# Keyboard_Controller.net
KiCad netlist of a schematic drawn in EAGLE
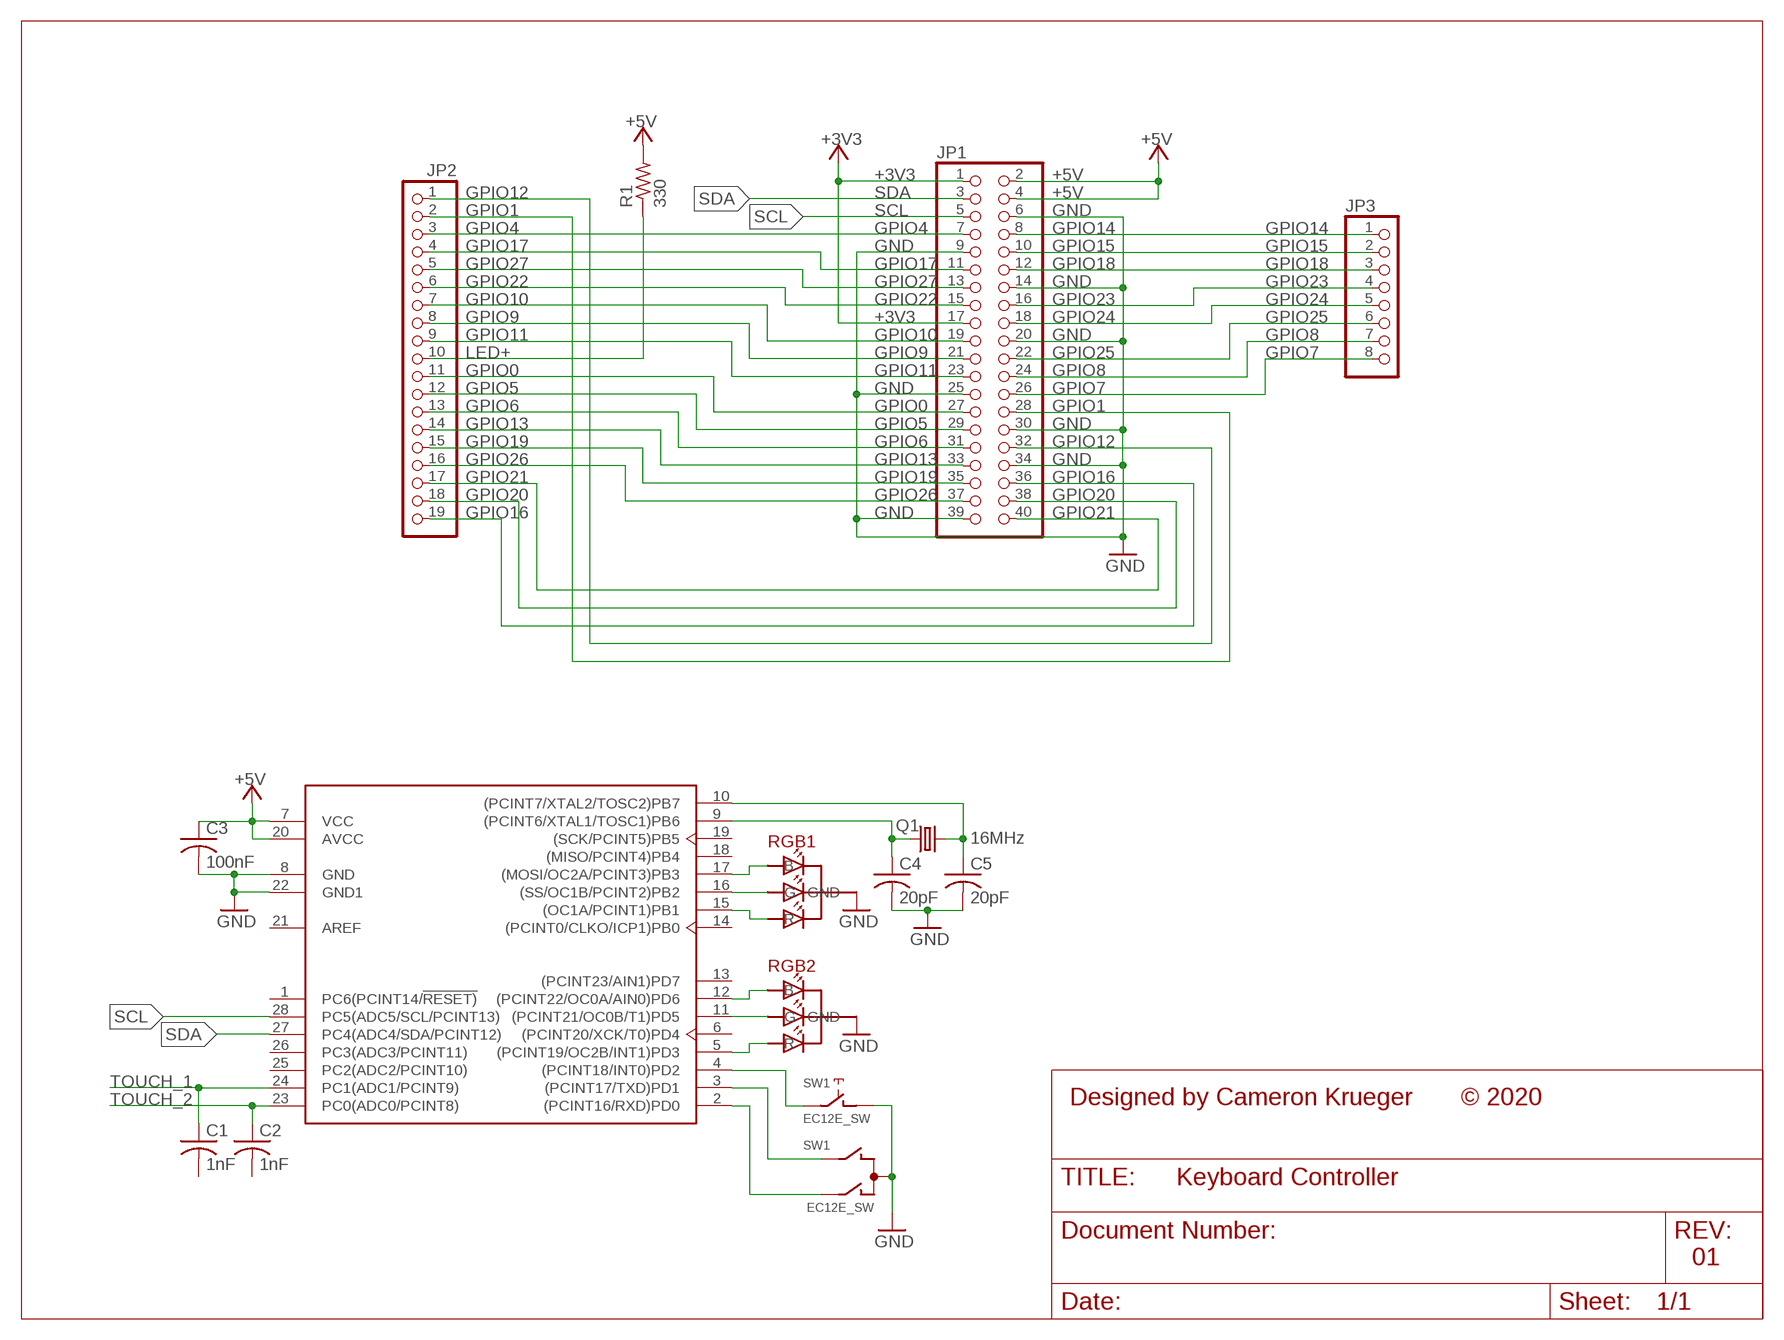
[diagram p0: schematic, sheet 1]

(export (version "E")
  (design (tool "Eeschema 10.0.6"))
  (components
    (comp (ref "C1")
      (value "1nF")
      (footprint "eagle-import:C025-030X050")
      (libsource (lib "eagle-import") (part "C-US025-030X050"))
    )
    (comp (ref "C2")
      (value "1nF")
      (footprint "eagle-import:C025-030X050")
      (libsource (lib "eagle-import") (part "C-US025-030X050"))
    )
    (comp (ref "C3")
      (value "100nF")
      (footprint "eagle-import:C050-024X044")
      (libsource (lib "eagle-import") (part "C-US050-024X044"))
    )
    (comp (ref "C4")
      (value "20pF")
      (footprint "eagle-import:C025-030X050")
      (libsource (lib "eagle-import") (part "C-US025-030X050"))
    )
    (comp (ref "C5")
      (value "20pF")
      (footprint "eagle-import:C025-030X050")
      (libsource (lib "eagle-import") (part "C-US025-030X050"))
    )
    (comp (ref "JP1")
      (value "PINHD-2X20")
      (footprint "eagle-import:2X20")
      (libsource (lib "eagle-import") (part "PINHD-2X20"))
    )
    (comp (ref "JP2")
      (value "PINHD-1X19")
      (footprint "eagle-import:1X19")
      (libsource (lib "eagle-import") (part "PINHD-1X19"))
    )
    (comp (ref "JP3")
      (value "PINHD-1X8")
      (footprint "eagle-import:1X08")
      (libsource (lib "eagle-import") (part "PINHD-1X8"))
    )
    (comp (ref "Q1")
      (value "16MHz")
      (footprint "eagle-import:HC49U-V")
      (libsource (lib "eagle-import") (part "CRYSTALHC49U-V"))
    )
    (comp (ref "R1")
      (value "330")
      (footprint "eagle-import:0207_10")
      (libsource (lib "eagle-import") (part "R-US_0207/10"))
    )
    (comp (ref "RGB1")
      (value "5MMRGBLED")
      (footprint "eagle-import:LED5MMRGB")
      (libsource (lib "eagle-import") (part "5MMRGBLED"))
    )
    (comp (ref "RGB2")
      (value "5MMRGBLED")
      (footprint "eagle-import:LED5MMRGB")
      (libsource (lib "eagle-import") (part "5MMRGBLED"))
    )
    (comp (ref "SW1")
      (value "EC12E_SW")
      (footprint "eagle-import:ALPS_EC12E_SW")
      (fields (field (name "MPN") "EC12E2424407"))
      (libsource (lib "eagle-import") (part "EC12E_SW"))
    )
    (comp (ref "U2")
      (value "ATMEGA328P-PU")
      (footprint "eagle-import:DIP-28")
      (fields
        (field (name "DIGIKEY_PART_NUMBER") "ATMEGA328P-PU-ND")
        (field (name "MANUFACTURER") "Microchip Technology")
        (field (name "CREATED_BY") "PCBLayout.com")
      )
      (libsource (lib "eagle-import") (part "ATMEGA328P-PU"))
    )
  )
  (nets
    (net (code "1") (name "+3V3") (class "Default")
      (node (ref "JP1") (pin "1") (pinfunction "1_1") (pintype "passive"))
      (node (ref "JP1") (pin "17") (pinfunction "17_17") (pintype "passive"))
    )
    (net (code "2") (name "+5V") (class "Default")
      (node (ref "C3") (pin "1") (pinfunction "1_1") (pintype "passive"))
      (node (ref "JP1") (pin "2") (pinfunction "2_2") (pintype "passive"))
      (node (ref "JP1") (pin "4") (pinfunction "4_4") (pintype "passive"))
      (node (ref "R1") (pin "2") (pinfunction "2_2") (pintype "passive"))
      (node (ref "U2") (pin "20") (pinfunction "AVCC_20") (pintype "power_in"))
      (node (ref "U2") (pin "7") (pinfunction "VCC_7") (pintype "power_in"))
    )
    (net (code "3") (name "/GPIO0") (class "Default")
      (node (ref "JP1") (pin "27") (pinfunction "27_27") (pintype "passive"))
      (node (ref "JP2") (pin "11") (pinfunction "11_11") (pintype "passive"))
    )
    (net (code "4") (name "/GPIO1") (class "Default")
      (node (ref "JP1") (pin "28") (pinfunction "28_28") (pintype "passive"))
      (node (ref "JP2") (pin "2") (pinfunction "2_2") (pintype "passive"))
    )
    (net (code "5") (name "/GPIO4") (class "Default")
      (node (ref "JP1") (pin "7") (pinfunction "7_7") (pintype "passive"))
      (node (ref "JP2") (pin "3") (pinfunction "3_3") (pintype "passive"))
    )
    (net (code "6") (name "/GPIO5") (class "Default")
      (node (ref "JP1") (pin "29") (pinfunction "29_29") (pintype "passive"))
      (node (ref "JP2") (pin "12") (pinfunction "12_12") (pintype "passive"))
    )
    (net (code "7") (name "/GPIO6") (class "Default")
      (node (ref "JP1") (pin "31") (pinfunction "31_31") (pintype "passive"))
      (node (ref "JP2") (pin "13") (pinfunction "13_13") (pintype "passive"))
    )
    (net (code "8") (name "/GPIO7") (class "Default")
      (node (ref "JP1") (pin "26") (pinfunction "26_26") (pintype "passive"))
      (node (ref "JP3") (pin "8") (pinfunction "8_8") (pintype "passive"))
    )
    (net (code "9") (name "/GPIO8") (class "Default")
      (node (ref "JP1") (pin "24") (pinfunction "24_24") (pintype "passive"))
      (node (ref "JP3") (pin "7") (pinfunction "7_7") (pintype "passive"))
    )
    (net (code "10") (name "/GPIO9") (class "Default")
      (node (ref "JP1") (pin "21") (pinfunction "21_21") (pintype "passive"))
      (node (ref "JP2") (pin "8") (pinfunction "8_8") (pintype "passive"))
    )
    (net (code "11") (name "/GPIO10") (class "Default")
      (node (ref "JP1") (pin "19") (pinfunction "19_19") (pintype "passive"))
      (node (ref "JP2") (pin "7") (pinfunction "7_7") (pintype "passive"))
    )
    (net (code "12") (name "/GPIO11") (class "Default")
      (node (ref "JP1") (pin "23") (pinfunction "23_23") (pintype "passive"))
      (node (ref "JP2") (pin "9") (pinfunction "9_9") (pintype "passive"))
    )
    (net (code "13") (name "/GPIO12") (class "Default")
      (node (ref "JP1") (pin "32") (pinfunction "32_32") (pintype "passive"))
      (node (ref "JP2") (pin "1") (pinfunction "1_1") (pintype "passive"))
    )
    (net (code "14") (name "/GPIO13") (class "Default")
      (node (ref "JP1") (pin "33") (pinfunction "33_33") (pintype "passive"))
      (node (ref "JP2") (pin "14") (pinfunction "14_14") (pintype "passive"))
    )
    (net (code "15") (name "/GPIO14") (class "Default")
      (node (ref "JP1") (pin "8") (pinfunction "8_8") (pintype "passive"))
      (node (ref "JP3") (pin "1") (pinfunction "1_1") (pintype "passive"))
    )
    (net (code "16") (name "/GPIO15") (class "Default")
      (node (ref "JP1") (pin "10") (pinfunction "10_10") (pintype "passive"))
      (node (ref "JP3") (pin "2") (pinfunction "2_2") (pintype "passive"))
    )
    (net (code "17") (name "/GPIO16") (class "Default")
      (node (ref "JP1") (pin "36") (pinfunction "36_36") (pintype "passive"))
      (node (ref "JP2") (pin "19") (pinfunction "19_19") (pintype "passive"))
    )
    (net (code "18") (name "/GPIO17") (class "Default")
      (node (ref "JP1") (pin "11") (pinfunction "11_11") (pintype "passive"))
      (node (ref "JP2") (pin "4") (pinfunction "4_4") (pintype "passive"))
    )
    (net (code "19") (name "/GPIO18") (class "Default")
      (node (ref "JP1") (pin "12") (pinfunction "12_12") (pintype "passive"))
      (node (ref "JP3") (pin "3") (pinfunction "3_3") (pintype "passive"))
    )
    (net (code "20") (name "/GPIO19") (class "Default")
      (node (ref "JP1") (pin "35") (pinfunction "35_35") (pintype "passive"))
      (node (ref "JP2") (pin "15") (pinfunction "15_15") (pintype "passive"))
    )
    (net (code "21") (name "/GPIO20") (class "Default")
      (node (ref "JP1") (pin "38") (pinfunction "38_38") (pintype "passive"))
      (node (ref "JP2") (pin "18") (pinfunction "18_18") (pintype "passive"))
    )
    (net (code "22") (name "/GPIO21") (class "Default")
      (node (ref "JP1") (pin "40") (pinfunction "40_40") (pintype "passive"))
      (node (ref "JP2") (pin "17") (pinfunction "17_17") (pintype "passive"))
    )
    (net (code "23") (name "/GPIO22") (class "Default")
      (node (ref "JP1") (pin "15") (pinfunction "15_15") (pintype "passive"))
      (node (ref "JP2") (pin "6") (pinfunction "6_6") (pintype "passive"))
    )
    (net (code "24") (name "/GPIO23") (class "Default")
      (node (ref "JP1") (pin "16") (pinfunction "16_16") (pintype "passive"))
      (node (ref "JP3") (pin "4") (pinfunction "4_4") (pintype "passive"))
    )
    (net (code "25") (name "/GPIO24") (class "Default")
      (node (ref "JP1") (pin "18") (pinfunction "18_18") (pintype "passive"))
      (node (ref "JP3") (pin "5") (pinfunction "5_5") (pintype "passive"))
    )
    (net (code "26") (name "/GPIO25") (class "Default")
      (node (ref "JP1") (pin "22") (pinfunction "22_22") (pintype "passive"))
      (node (ref "JP3") (pin "6") (pinfunction "6_6") (pintype "passive"))
    )
    (net (code "27") (name "/GPIO26") (class "Default")
      (node (ref "JP1") (pin "37") (pinfunction "37_37") (pintype "passive"))
      (node (ref "JP2") (pin "16") (pinfunction "16_16") (pintype "passive"))
    )
    (net (code "28") (name "/GPIO27") (class "Default")
      (node (ref "JP1") (pin "13") (pinfunction "13_13") (pintype "passive"))
      (node (ref "JP2") (pin "5") (pinfunction "5_5") (pintype "passive"))
    )
    (net (code "29") (name "/LED+") (class "Default")
      (node (ref "JP2") (pin "10") (pinfunction "10_10") (pintype "passive"))
      (node (ref "R1") (pin "1") (pinfunction "1_1") (pintype "passive"))
    )
    (net (code "30") (name "/TOUCH_1") (class "Default")
      (node (ref "C1") (pin "1") (pinfunction "1_1") (pintype "passive"))
      (node (ref "U2") (pin "24") (pinfunction "PC1(ADC1/PCINT9)_24") (pintype "bidirectional"))
    )
    (net (code "31") (name "/TOUCH_2") (class "Default")
      (node (ref "C2") (pin "1") (pinfunction "1_1") (pintype "passive"))
      (node (ref "U2") (pin "23") (pinfunction "PC0(ADC0/PCINT8)_23") (pintype "bidirectional"))
    )
    (net (code "32") (name "GND") (class "Default")
      (node (ref "C3") (pin "2") (pinfunction "2_2") (pintype "passive"))
      (node (ref "C4") (pin "2") (pinfunction "2_2") (pintype "passive"))
      (node (ref "C5") (pin "2") (pinfunction "2_2") (pintype "passive"))
      (node (ref "JP1") (pin "14") (pinfunction "14_14") (pintype "passive"))
      (node (ref "JP1") (pin "20") (pinfunction "20_20") (pintype "passive"))
      (node (ref "JP1") (pin "25") (pinfunction "25_25") (pintype "passive"))
      (node (ref "JP1") (pin "30") (pinfunction "30_30") (pintype "passive"))
      (node (ref "JP1") (pin "34") (pinfunction "34_34") (pintype "passive"))
      (node (ref "JP1") (pin "39") (pinfunction "39_39") (pintype "passive"))
      (node (ref "JP1") (pin "6") (pinfunction "6_6") (pintype "passive"))
      (node (ref "JP1") (pin "9") (pinfunction "9_9") (pintype "passive"))
      (node (ref "RGB1") (pin "P$3") (pinfunction "GND_P$3") (pintype "bidirectional"))
      (node (ref "RGB2") (pin "P$3") (pinfunction "GND_P$3") (pintype "bidirectional"))
      (node (ref "SW1") (pin "C") (pinfunction "C_C") (pintype "passive"))
      (node (ref "SW1") (pin "D") (pinfunction "1_D") (pintype "passive"))
      (node (ref "U2") (pin "22") (pinfunction "GND1_22") (pintype "power_in"))
      (node (ref "U2") (pin "8") (pinfunction "GND_8") (pintype "power_in"))
    )
    (net (code "33") (name "Net-(RGB1-B)") (class "Default")
      (node (ref "RGB1") (pin "P$1") (pinfunction "B_P$1") (pintype "bidirectional"))
      (node (ref "U2") (pin "17") (pinfunction "(MOSI/OC2A/PCINT3)PB3_17") (pintype "bidirectional"))
    )
    (net (code "34") (name "Net-(RGB1-G)") (class "Default")
      (node (ref "RGB1") (pin "P$2") (pinfunction "G_P$2") (pintype "bidirectional"))
      (node (ref "U2") (pin "16") (pinfunction "(SS/OC1B/PCINT2)PB2_16") (pintype "bidirectional"))
    )
    (net (code "35") (name "Net-(RGB1-R)") (class "Default")
      (node (ref "RGB1") (pin "P$4") (pinfunction "R_P$4") (pintype "bidirectional"))
      (node (ref "U2") (pin "15") (pinfunction "(OC1A/PCINT1)PB1_15") (pintype "bidirectional"))
    )
    (net (code "36") (name "Net-(RGB2-B)") (class "Default")
      (node (ref "RGB2") (pin "P$1") (pinfunction "B_P$1") (pintype "bidirectional"))
      (node (ref "U2") (pin "12") (pinfunction "(PCINT22/OC0A/AIN0)PD6_12") (pintype "bidirectional"))
    )
    (net (code "37") (name "Net-(RGB2-G)") (class "Default")
      (node (ref "RGB2") (pin "P$2") (pinfunction "G_P$2") (pintype "bidirectional"))
      (node (ref "U2") (pin "11") (pinfunction "(PCINT21/OC0B/T1)PD5_11") (pintype "bidirectional"))
    )
    (net (code "38") (name "Net-(RGB2-R)") (class "Default")
      (node (ref "RGB2") (pin "P$4") (pinfunction "R_P$4") (pintype "bidirectional"))
      (node (ref "U2") (pin "5") (pinfunction "(PCINT19/OC2B/INT1)PD3_5") (pintype "bidirectional"))
    )
    (net (code "39") (name "Net-(SW1B-2)") (class "Default")
      (node (ref "SW1") (pin "E") (pinfunction "2_E") (pintype "passive"))
      (node (ref "U2") (pin "4") (pinfunction "(PCINT18/INT0)PD2_4") (pintype "bidirectional"))
    )
    (net (code "40") (name "Net-(U2-(PCINT6{slash}XTAL1{slash}TOSC1)PB6)") (class "Default")
      (node (ref "C4") (pin "1") (pinfunction "1_1") (pintype "passive"))
      (node (ref "Q1") (pin "1") (pinfunction "1_1") (pintype "passive"))
      (node (ref "U2") (pin "9") (pinfunction "(PCINT6/XTAL1/TOSC1)PB6_9") (pintype "bidirectional"))
    )
    (net (code "41") (name "Net-(U2-(PCINT7{slash}XTAL2{slash}TOSC2)PB7)") (class "Default")
      (node (ref "C5") (pin "1") (pinfunction "1_1") (pintype "passive"))
      (node (ref "Q1") (pin "2") (pinfunction "2_2") (pintype "passive"))
      (node (ref "U2") (pin "10") (pinfunction "(PCINT7/XTAL2/TOSC2)PB7_10") (pintype "bidirectional"))
    )
    (net (code "42") (name "Net-(U2-(PCINT16{slash}RXD)PD0)") (class "Default")
      (node (ref "SW1") (pin "A") (pinfunction "A_A") (pintype "passive"))
      (node (ref "U2") (pin "2") (pinfunction "(PCINT16/RXD)PD0_2") (pintype "bidirectional"))
    )
    (net (code "43") (name "Net-(U2-(PCINT17{slash}TXD)PD1)") (class "Default")
      (node (ref "SW1") (pin "B") (pinfunction "B_B") (pintype "passive"))
      (node (ref "U2") (pin "3") (pinfunction "(PCINT17/TXD)PD1_3") (pintype "bidirectional"))
    )
    (net (code "44") (name "SCL") (class "Default")
      (node (ref "JP1") (pin "5") (pinfunction "5_5") (pintype "passive"))
      (node (ref "U2") (pin "28") (pinfunction "PC5(ADC5/SCL/PCINT13)_28") (pintype "bidirectional"))
    )
    (net (code "45") (name "SDA") (class "Default")
      (node (ref "JP1") (pin "3") (pinfunction "3_3") (pintype "passive"))
      (node (ref "U2") (pin "27") (pinfunction "PC4(ADC4/SDA/PCINT12)_27") (pintype "bidirectional"))
    )
    (net (code "46") (name "unconnected-(C1-Pad2)") (class "Default")
      (node (ref "C1") (pin "2") (pinfunction "2_2") (pintype "passive"))
    )
    (net (code "47") (name "unconnected-(C2-Pad2)") (class "Default")
      (node (ref "C2") (pin "2") (pinfunction "2_2") (pintype "passive"))
    )
    (net (code "48") (name "unconnected-(U2-(MISO{slash}PCINT4)PB4-Pad18)") (class "Default")
      (node (ref "U2") (pin "18") (pinfunction "(MISO/PCINT4)PB4_18") (pintype "bidirectional"))
    )
    (net (code "49") (name "unconnected-(U2-(PCINT0{slash}CLKO{slash}ICP1)PB0-Pad14)") (class "Default")
      (node (ref "U2") (pin "14") (pinfunction "(PCINT0/CLKO/ICP1)PB0_14") (pintype "bidirectional"))
    )
    (net (code "50") (name "unconnected-(U2-(PCINT20{slash}XCK{slash}T0)PD4-Pad6)") (class "Default")
      (node (ref "U2") (pin "6") (pinfunction "(PCINT20/XCK/T0)PD4_6") (pintype "bidirectional"))
    )
    (net (code "51") (name "unconnected-(U2-(PCINT23{slash}AIN1)PD7-Pad13)") (class "Default")
      (node (ref "U2") (pin "13") (pinfunction "(PCINT23/AIN1)PD7_13") (pintype "bidirectional"))
    )
    (net (code "52") (name "unconnected-(U2-(SCK{slash}PCINT5)PB5-Pad19)") (class "Default")
      (node (ref "U2") (pin "19") (pinfunction "(SCK/PCINT5)PB5_19") (pintype "bidirectional"))
    )
    (net (code "53") (name "unconnected-(U2-AREF-Pad21)") (class "Default")
      (node (ref "U2") (pin "21") (pinfunction "AREF_21") (pintype "input"))
    )
    (net (code "54") (name "unconnected-(U2-PC2(ADC2{slash}PCINT10)-Pad25)") (class "Default")
      (node (ref "U2") (pin "25") (pinfunction "PC2(ADC2/PCINT10)_25") (pintype "bidirectional"))
    )
    (net (code "55") (name "unconnected-(U2-PC3(ADC3{slash}PCINT11)-Pad26)") (class "Default")
      (node (ref "U2") (pin "26") (pinfunction "PC3(ADC3/PCINT11)_26") (pintype "bidirectional"))
    )
    (net (code "56") (name "unconnected-(U2-PC6(PCINT14{slash}~{RESET})-Pad1)") (class "Default")
      (node (ref "U2") (pin "1") (pinfunction "PC6(PCINT14/~{RESET})_1") (pintype "bidirectional"))
    )
  )
)
